# schematic-version3_-_Jigbin.net
KiCad netlist of a schematic drawn in EAGLE
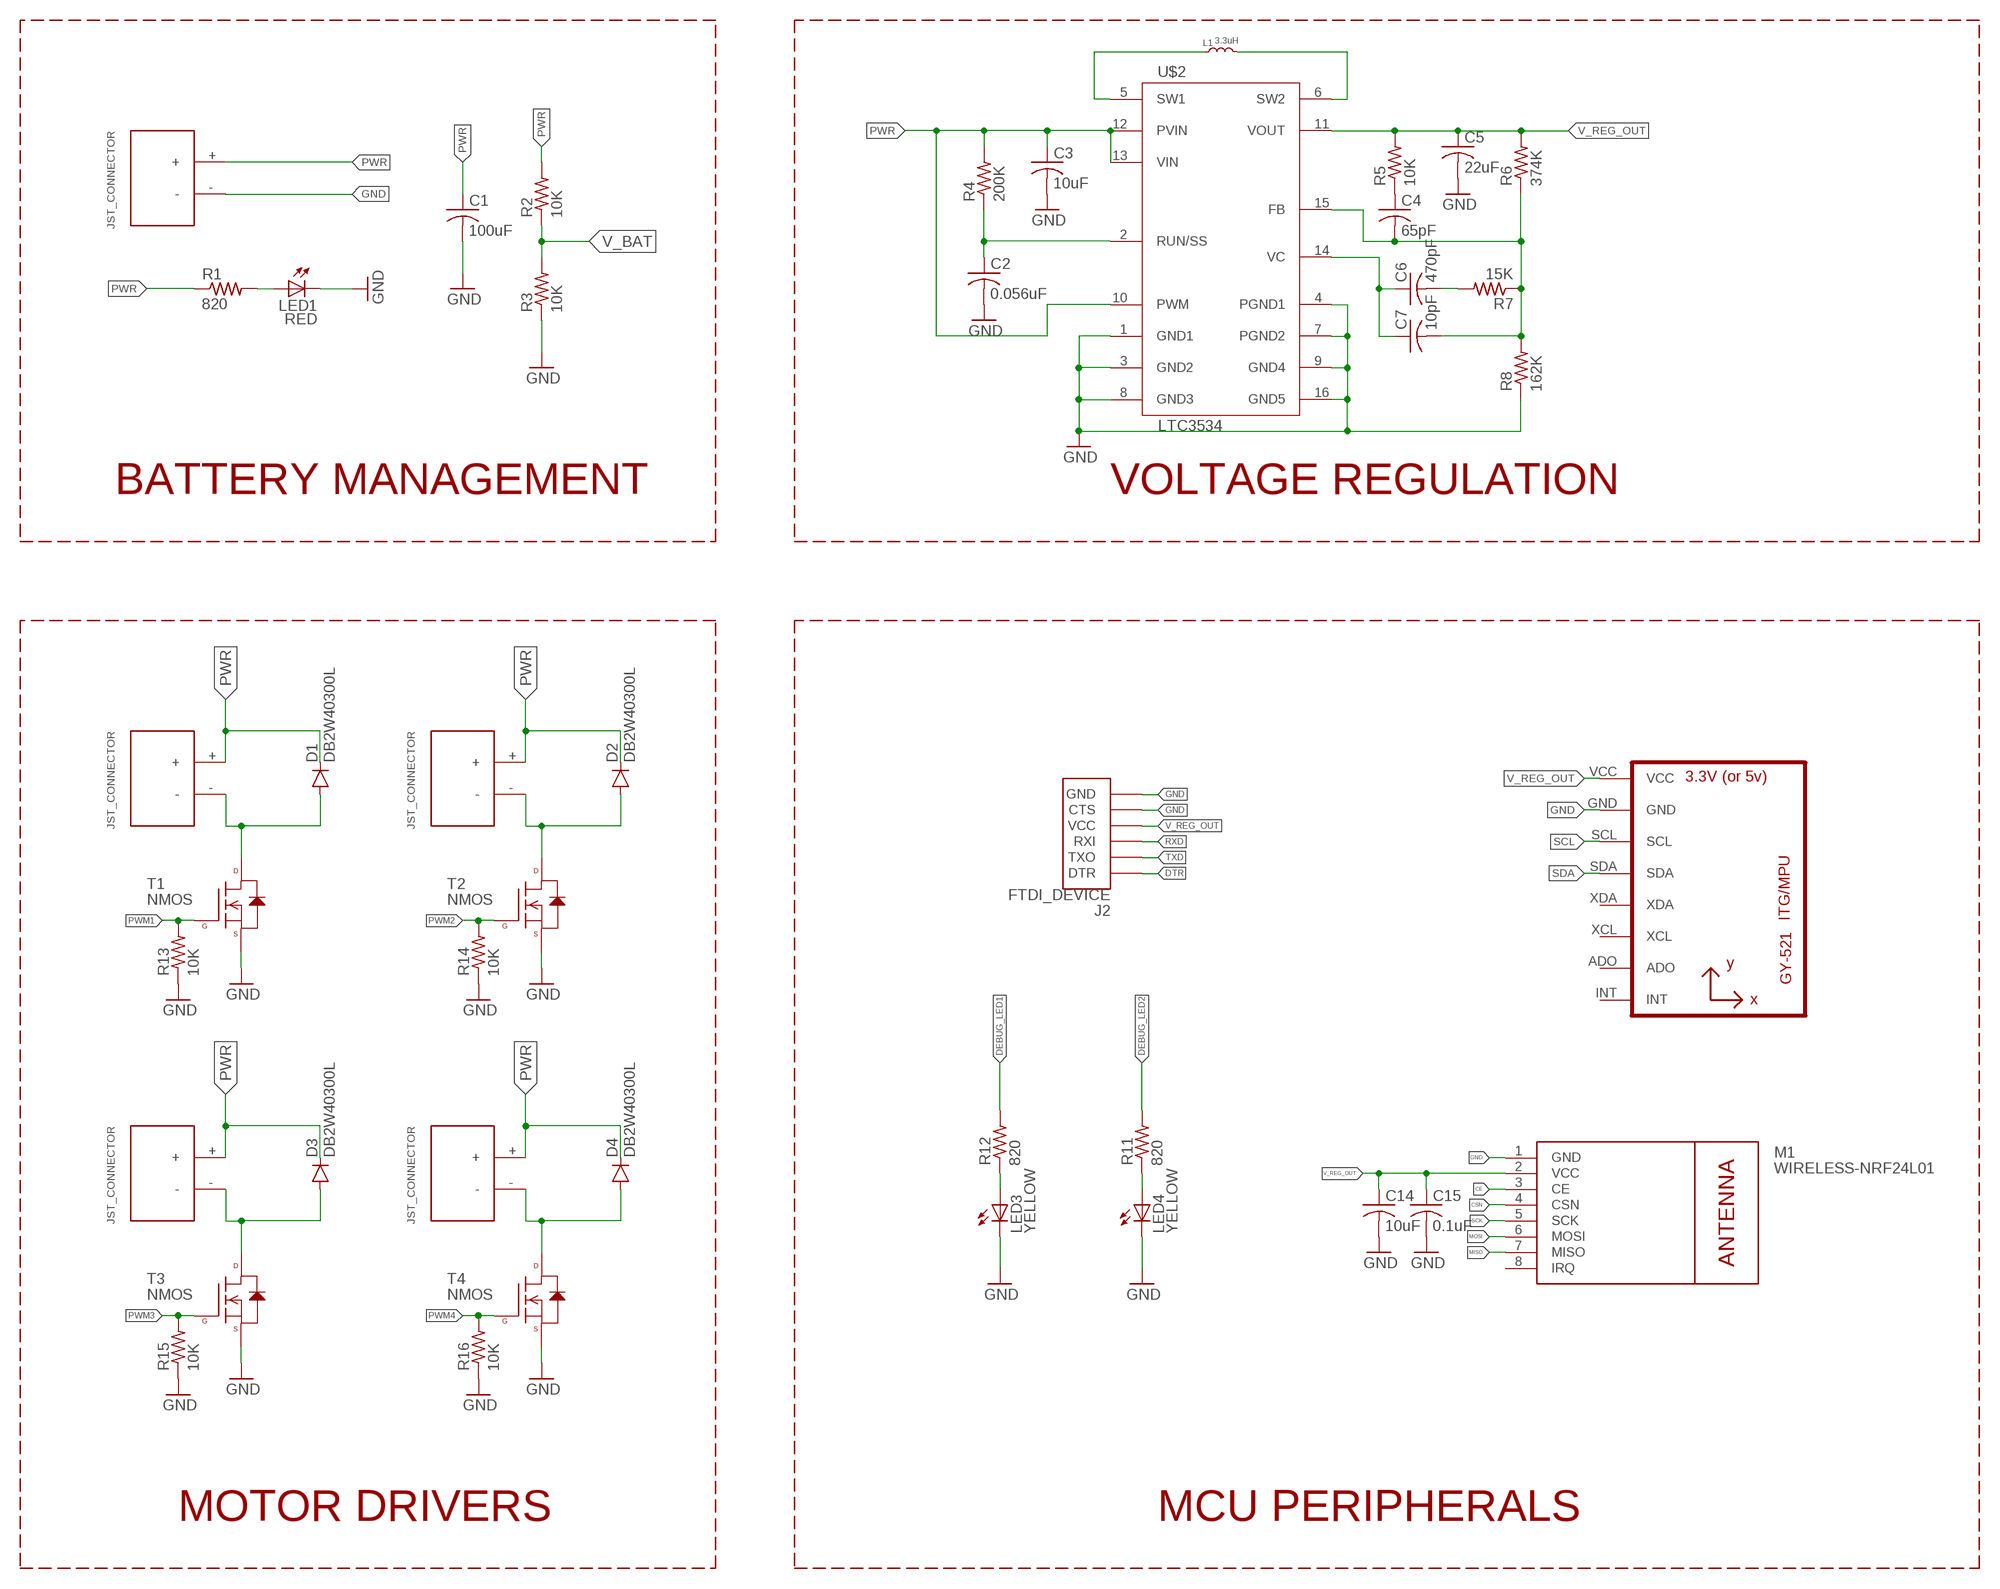
[diagram p0: schematic, sheet 1, part 1 of 2]
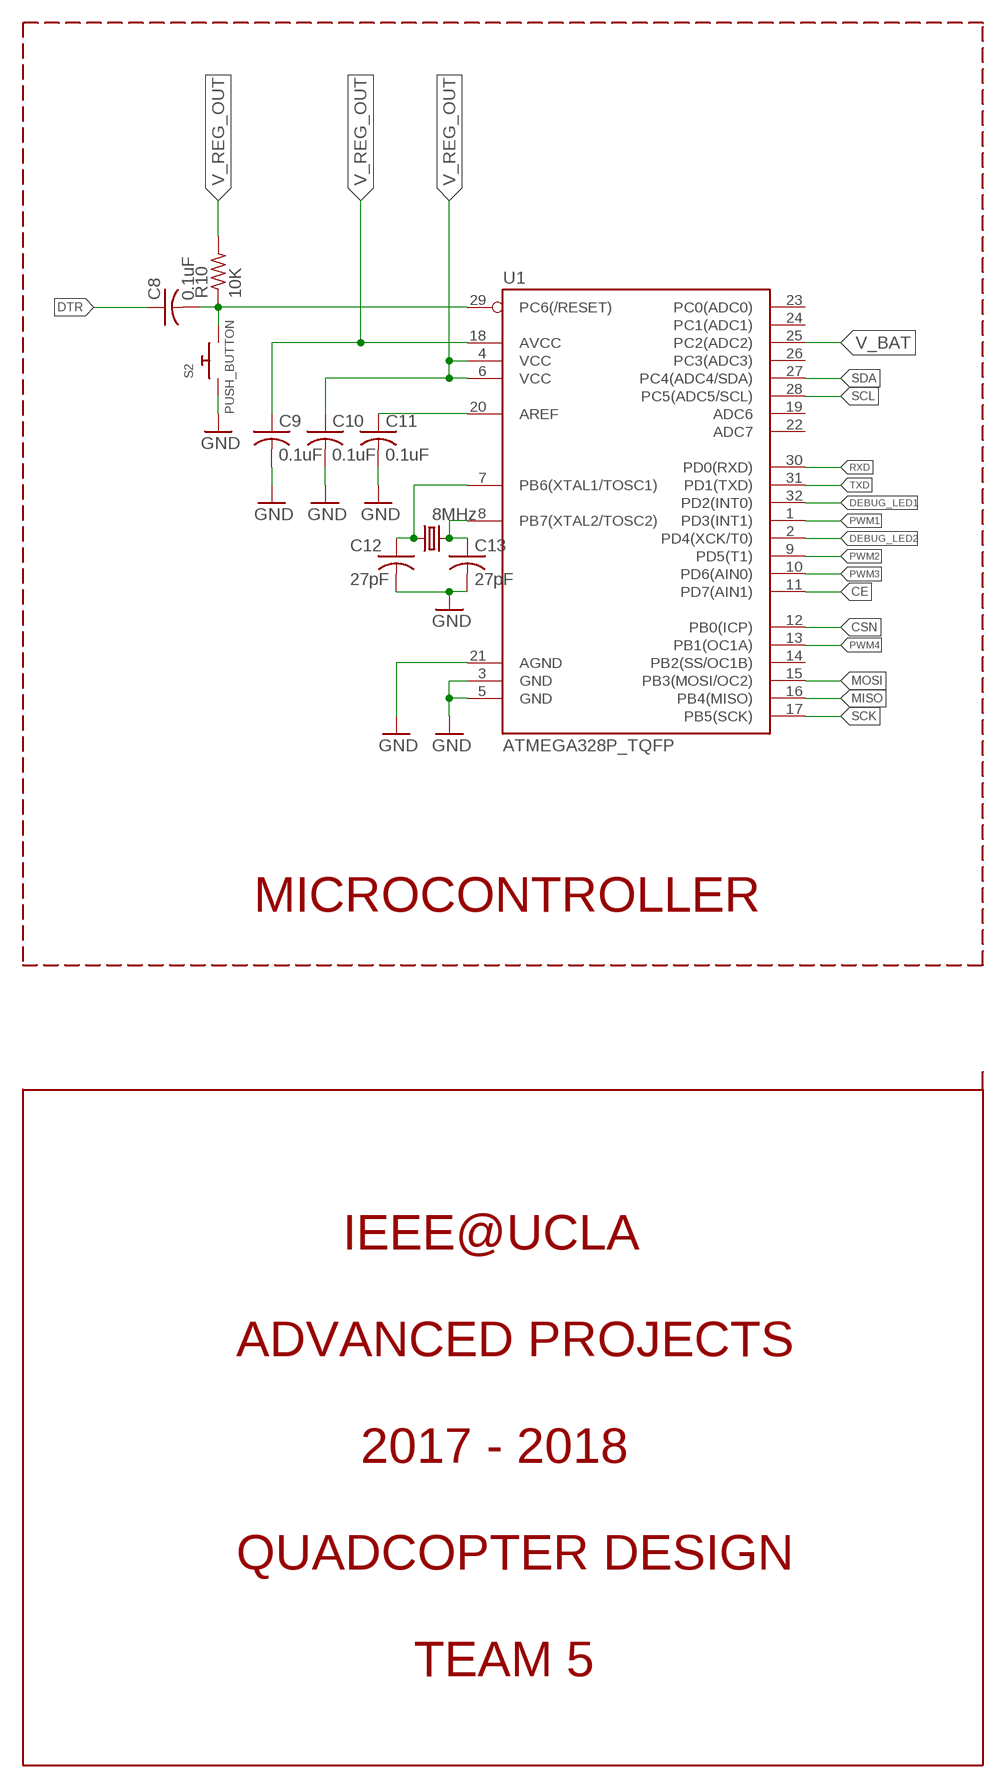
[diagram p1: schematic, sheet 1, part 2 of 2]

(export (version "E")
  (design (tool "Eeschema 10.0.6"))
  (components
    (comp (ref "C1")
      (value "100uF")
      (footprint "eagle-import:C1210")
      (libsource (lib "eagle-import") (part "C-USC1210"))
    )
    (comp (ref "C2")
      (value "0.056uF")
      (footprint "eagle-import:C0603")
      (libsource (lib "eagle-import") (part "resistor_348_C-USC0603"))
    )
    (comp (ref "C3")
      (value "10uF")
      (footprint "eagle-import:C0603")
      (libsource (lib "eagle-import") (part "resistor_348_C-USC0603"))
    )
    (comp (ref "C4")
      (value "65pF")
      (footprint "eagle-import:C1206")
      (libsource (lib "eagle-import") (part "C-USC1206"))
    )
    (comp (ref "C5")
      (value "22uF")
      (footprint "eagle-import:C0603")
      (libsource (lib "eagle-import") (part "resistor_348_C-USC0603"))
    )
    (comp (ref "C6")
      (value "470pF")
      (footprint "eagle-import:C0603")
      (libsource (lib "eagle-import") (part "resistor_348_C-USC0603"))
    )
    (comp (ref "C7")
      (value "10pF")
      (footprint "eagle-import:C0603")
      (libsource (lib "eagle-import") (part "resistor_348_C-USC0603"))
    )
    (comp (ref "C8")
      (value "0.1uF")
      (footprint "eagle-import:C0603")
      (libsource (lib "eagle-import") (part "C-USC0603"))
    )
    (comp (ref "C9")
      (value "0.1uF")
      (footprint "eagle-import:C0603")
      (libsource (lib "eagle-import") (part "C-USC0603"))
    )
    (comp (ref "C10")
      (value "0.1uF")
      (footprint "eagle-import:C0603")
      (libsource (lib "eagle-import") (part "C-USC0603"))
    )
    (comp (ref "C11")
      (value "0.1uF")
      (footprint "eagle-import:C0603")
      (libsource (lib "eagle-import") (part "C-USC0603"))
    )
    (comp (ref "C12")
      (value "27pF")
      (footprint "eagle-import:C0603")
      (libsource (lib "eagle-import") (part "resistor_348_C-USC0603"))
    )
    (comp (ref "C13")
      (value "27pF")
      (footprint "eagle-import:C0603")
      (libsource (lib "eagle-import") (part "resistor_348_C-USC0603"))
    )
    (comp (ref "C14")
      (value "10uF")
      (footprint "eagle-import:C0603")
      (libsource (lib "eagle-import") (part "resistor_348_C-USC0603"))
    )
    (comp (ref "C15")
      (value "0.1uF")
      (footprint "eagle-import:C0603")
      (libsource (lib "eagle-import") (part "resistor_348_C-USC0603"))
    )
    (comp (ref "D1")
      (value "DB2W40300L")
      (footprint "eagle-import:MINI2-F3-B")
      (libsource (lib "eagle-import") (part "DB2W40300L"))
    )
    (comp (ref "D2")
      (value "DB2W40300L")
      (footprint "eagle-import:MINI2-F3-B")
      (libsource (lib "eagle-import") (part "DB2W40300L"))
    )
    (comp (ref "D3")
      (value "DB2W40300L")
      (footprint "eagle-import:MINI2-F3-B")
      (libsource (lib "eagle-import") (part "DB2W40300L"))
    )
    (comp (ref "D4")
      (value "DB2W40300L")
      (footprint "eagle-import:MINI2-F3-B")
      (libsource (lib "eagle-import") (part "DB2W40300L"))
    )
    (comp (ref "J2")
      (value "FTDI_DEVICE")
      (footprint "eagle-import:FTDI_DEVICE_SIDE")
      (libsource (lib "eagle-import") (part "FTDI_DEVICE"))
    )
    (comp (ref "L1")
      (value "3.3uH")
      (footprint "eagle-import:XAL4020")
      (libsource (lib "eagle-import") (part "INDUCTOR.XAL4020"))
    )
    (comp (ref "LED1")
      (value "RED")
      (footprint "eagle-import:SML0603")
      (libsource (lib "eagle-import") (part "LEDSML0603"))
    )
    (comp (ref "LED3")
      (value "YELLOW")
      (footprint "eagle-import:SML0603")
      (libsource (lib "eagle-import") (part "LEDSML0603"))
    )
    (comp (ref "LED4")
      (value "YELLOW")
      (footprint "eagle-import:SML0603")
      (libsource (lib "eagle-import") (part "LEDSML0603"))
    )
    (comp (ref "M1")
      (value "WIRELESS-NRF24L01")
      (footprint "eagle-import:WIRELESS-NRF24L01")
      (libsource (lib "eagle-import") (part "WIRELESS-NRF24L01"))
    )
    (comp (ref "Q1")
      (value "8MHz")
      (footprint "eagle-import:CSM-7X-DU")
      (libsource (lib "eagle-import") (part "CSM-7X-DU"))
    )
    (comp (ref "R1")
      (value "820")
      (footprint "eagle-import:R0603")
      (libsource (lib "eagle-import") (part "R-US_R0603"))
    )
    (comp (ref "R2")
      (value "10K")
      (footprint "eagle-import:R0603")
      (libsource (lib "eagle-import") (part "resistor_348_R-US_R0603"))
    )
    (comp (ref "R3")
      (value "10K")
      (footprint "eagle-import:R0603")
      (libsource (lib "eagle-import") (part "resistor_348_R-US_R0603"))
    )
    (comp (ref "R4")
      (value "200K")
      (footprint "eagle-import:R0603")
      (libsource (lib "eagle-import") (part "resistor_348_R-US_R0603"))
    )
    (comp (ref "R5")
      (value "10K")
      (footprint "eagle-import:R0603")
      (libsource (lib "eagle-import") (part "resistor_348_R-US_R0603"))
    )
    (comp (ref "R6")
      (value "374K")
      (footprint "eagle-import:R0603")
      (libsource (lib "eagle-import") (part "resistor_348_R-US_R0603"))
    )
    (comp (ref "R7")
      (value "15K")
      (footprint "eagle-import:R0603")
      (libsource (lib "eagle-import") (part "resistor_348_R-US_R0603"))
    )
    (comp (ref "R8")
      (value "162K")
      (footprint "eagle-import:R0603")
      (libsource (lib "eagle-import") (part "resistor_348_R-US_R0603"))
    )
    (comp (ref "R10")
      (value "10K")
      (footprint "eagle-import:R0603")
      (libsource (lib "eagle-import") (part "resistor_348_R-US_R0603"))
    )
    (comp (ref "R11")
      (value "820")
      (footprint "eagle-import:R0603")
      (libsource (lib "eagle-import") (part "R-US_R0603"))
    )
    (comp (ref "R12")
      (value "820")
      (footprint "eagle-import:R0603")
      (libsource (lib "eagle-import") (part "R-US_R0603"))
    )
    (comp (ref "R13")
      (value "10K")
      (footprint "eagle-import:R0603")
      (libsource (lib "eagle-import") (part "resistor_348_R-US_R0603"))
    )
    (comp (ref "R14")
      (value "10K")
      (footprint "eagle-import:R0603")
      (libsource (lib "eagle-import") (part "resistor_348_R-US_R0603"))
    )
    (comp (ref "R15")
      (value "10K")
      (footprint "eagle-import:R0603")
      (libsource (lib "eagle-import") (part "resistor_348_R-US_R0603"))
    )
    (comp (ref "R16")
      (value "10K")
      (footprint "eagle-import:R0603")
      (libsource (lib "eagle-import") (part "resistor_348_R-US_R0603"))
    )
    (comp (ref "S2")
      (value "PUSH_BUTTON")
      (footprint "eagle-import:PUSHBUTTON_SMD_SJ")
      (libsource (lib "eagle-import") (part "SWITCH_PUSHBUTTONSOFTTOUCHSMD_SJ"))
    )
    (comp (ref "T1")
      (value "NMOS")
      (footprint "eagle-import:SOT23-3")
      (libsource (lib "eagle-import") (part "N-CHANNEL-MOSFET-IRLML6244TRPBF"))
    )
    (comp (ref "T2")
      (value "NMOS")
      (footprint "eagle-import:SOT23-3")
      (libsource (lib "eagle-import") (part "N-CHANNEL-MOSFET-IRLML6244TRPBF"))
    )
    (comp (ref "T3")
      (value "NMOS")
      (footprint "eagle-import:SOT23-3")
      (libsource (lib "eagle-import") (part "N-CHANNEL-MOSFET-IRLML6244TRPBF"))
    )
    (comp (ref "T4")
      (value "NMOS")
      (footprint "eagle-import:SOT23-3")
      (libsource (lib "eagle-import") (part "N-CHANNEL-MOSFET-IRLML6244TRPBF"))
    )
    (comp (ref "U$1")
      (value "JST_CONNECTOR_FEMALE")
      (footprint "eagle-import:JST_CONNECTOR_FEMALE")
      (libsource (lib "eagle-import") (part "JST_CONNECTOR_FEMALE"))
    )
    (comp (ref "U$2")
      (value "LTC3534")
      (footprint "eagle-import:SSOP-16GN")
      (libsource (lib "eagle-import") (part "LTC3534"))
    )
    (comp (ref "U$4")
      (value "JST_CONNECTOR_FEMALE")
      (footprint "eagle-import:JST_CONNECTOR_FEMALE")
      (libsource (lib "eagle-import") (part "JST_CONNECTOR_FEMALE"))
    )
    (comp (ref "U$7")
      (value "JST_CONNECTOR_FEMALE")
      (footprint "eagle-import:JST_CONNECTOR_FEMALE")
      (libsource (lib "eagle-import") (part "JST_CONNECTOR_FEMALE"))
    )
    (comp (ref "U$10")
      (value "JST_CONNECTOR_FEMALE")
      (footprint "eagle-import:JST_CONNECTOR_FEMALE")
      (libsource (lib "eagle-import") (part "JST_CONNECTOR_FEMALE"))
    )
    (comp (ref "U$13")
      (value "JST_CONNECTOR_FEMALE")
      (footprint "eagle-import:JST_CONNECTOR_FEMALE")
      (libsource (lib "eagle-import") (part "JST_CONNECTOR_FEMALE"))
    )
    (comp (ref "U1")
      (value "ATMEGA328P_TQFP")
      (footprint "eagle-import:TQFP32-08")
      (libsource (lib "eagle-import") (part "ATMEGA328P_TQFP"))
    )
    (comp (ref "U2")
      (value "GY-521MPU6050")
      (footprint "eagle-import:GY-521")
      (libsource (lib "eagle-import") (part "GY-521MPU6050"))
    )
  )
  (nets
    (net (code "1") (name "CE") (class "Default")
      (node (ref "M1") (pin "3") (pinfunction "CE_3") (pintype "bidirectional"))
      (node (ref "U1") (pin "11") (pinfunction "PD7(AIN1)_11") (pintype "bidirectional"))
    )
    (net (code "2") (name "CSN") (class "Default")
      (node (ref "M1") (pin "4") (pinfunction "CSN_4") (pintype "bidirectional"))
      (node (ref "U1") (pin "12") (pinfunction "PB0(ICP)_12") (pintype "bidirectional"))
    )
    (net (code "3") (name "DEBUG_LED1") (class "Default")
      (node (ref "R12") (pin "2") (pinfunction "2_2") (pintype "passive"))
      (node (ref "U1") (pin "32") (pinfunction "PD2(INT0)_32") (pintype "bidirectional"))
    )
    (net (code "4") (name "DEBUG_LED2") (class "Default")
      (node (ref "R11") (pin "2") (pinfunction "2_2") (pintype "passive"))
      (node (ref "U1") (pin "2") (pinfunction "PD4(XCK/T0)_2") (pintype "bidirectional"))
    )
    (net (code "5") (name "DTR") (class "Default")
      (node (ref "C8") (pin "1") (pinfunction "1_1") (pintype "passive"))
      (node (ref "J2") (pin "P$1") (pinfunction "DTR_P$1") (pintype "bidirectional"))
    )
    (net (code "6") (name "GND") (class "Default")
      (node (ref "C1") (pin "2") (pinfunction "2_2") (pintype "passive"))
      (node (ref "C10") (pin "2") (pinfunction "2_2") (pintype "passive"))
      (node (ref "C11") (pin "2") (pinfunction "2_2") (pintype "passive"))
      (node (ref "C12") (pin "2") (pinfunction "2_2") (pintype "passive"))
      (node (ref "C13") (pin "2") (pinfunction "2_2") (pintype "passive"))
      (node (ref "C14") (pin "2") (pinfunction "2_2") (pintype "passive"))
      (node (ref "C15") (pin "2") (pinfunction "2_2") (pintype "passive"))
      (node (ref "C2") (pin "2") (pinfunction "2_2") (pintype "passive"))
      (node (ref "C3") (pin "2") (pinfunction "2_2") (pintype "passive"))
      (node (ref "C5") (pin "2") (pinfunction "2_2") (pintype "passive"))
      (node (ref "C9") (pin "2") (pinfunction "2_2") (pintype "passive"))
      (node (ref "J2") (pin "P$5") (pinfunction "CTS_P$5") (pintype "bidirectional"))
      (node (ref "J2") (pin "P$6") (pinfunction "GND_P$6") (pintype "bidirectional"))
      (node (ref "LED1") (pin "C") (pinfunction "C_C") (pintype "passive"))
      (node (ref "LED3") (pin "C") (pinfunction "C_C") (pintype "passive"))
      (node (ref "LED4") (pin "C") (pinfunction "C_C") (pintype "passive"))
      (node (ref "M1") (pin "1") (pinfunction "GND_1") (pintype "power_in"))
      (node (ref "R13") (pin "1") (pinfunction "1_1") (pintype "passive"))
      (node (ref "R14") (pin "1") (pinfunction "1_1") (pintype "passive"))
      (node (ref "R15") (pin "1") (pinfunction "1_1") (pintype "passive"))
      (node (ref "R16") (pin "1") (pinfunction "1_1") (pintype "passive"))
      (node (ref "R3") (pin "1") (pinfunction "1_1") (pintype "passive"))
      (node (ref "R8") (pin "1") (pinfunction "1_1") (pintype "passive"))
      (node (ref "S2") (pin "P$1") (pinfunction "P$1_P$1") (pintype "passive"))
      (node (ref "T1") (pin "2") (pinfunction "S_2") (pintype "passive"))
      (node (ref "T2") (pin "2") (pinfunction "S_2") (pintype "passive"))
      (node (ref "T3") (pin "2") (pinfunction "S_2") (pintype "passive"))
      (node (ref "T4") (pin "2") (pinfunction "S_2") (pintype "passive"))
      (node (ref "U$1") (pin "-") (pinfunction "-_-") (pintype "bidirectional"))
      (node (ref "U$2") (pin "1") (pinfunction "GND1_1") (pintype "bidirectional"))
      (node (ref "U$2") (pin "16") (pinfunction "GND5_16") (pintype "bidirectional"))
      (node (ref "U$2") (pin "3") (pinfunction "GND2_3") (pintype "bidirectional"))
      (node (ref "U$2") (pin "4") (pinfunction "PGND1_4") (pintype "bidirectional"))
      (node (ref "U$2") (pin "7") (pinfunction "PGND2_7") (pintype "bidirectional"))
      (node (ref "U$2") (pin "8") (pinfunction "GND3_8") (pintype "bidirectional"))
      (node (ref "U$2") (pin "9") (pinfunction "GND4_9") (pintype "bidirectional"))
      (node (ref "U1") (pin "21") (pinfunction "AGND_21") (pintype "bidirectional"))
      (node (ref "U1") (pin "3") (pinfunction "GND_3") (pintype "bidirectional"))
      (node (ref "U1") (pin "5") (pinfunction "GND_5") (pintype "bidirectional"))
      (node (ref "U2") (pin "GND") (pinfunction "GND_GND") (pintype "bidirectional"))
    )
    (net (code "7") (name "MISO") (class "Default")
      (node (ref "M1") (pin "7") (pinfunction "MISO_7") (pintype "bidirectional"))
      (node (ref "U1") (pin "16") (pinfunction "PB4(MISO)_16") (pintype "bidirectional"))
    )
    (net (code "8") (name "MOSI") (class "Default")
      (node (ref "M1") (pin "6") (pinfunction "MOSI_6") (pintype "bidirectional"))
      (node (ref "U1") (pin "15") (pinfunction "PB3(MOSI/OC2)_15") (pintype "bidirectional"))
    )
    (net (code "9") (name "Net-(C4-Pad1)") (class "Default")
      (node (ref "C4") (pin "1") (pinfunction "1_1") (pintype "passive"))
      (node (ref "R5") (pin "1") (pinfunction "1_1") (pintype "passive"))
    )
    (net (code "10") (name "Net-(C6-Pad2)") (class "Default")
      (node (ref "C6") (pin "2") (pinfunction "2_2") (pintype "passive"))
      (node (ref "R7") (pin "2") (pinfunction "2_2") (pintype "passive"))
    )
    (net (code "11") (name "Net-(D1-PPIN)") (class "Default")
      (node (ref "D1") (pin "POS") (pinfunction "PPIN_POS") (pintype "passive"))
      (node (ref "T1") (pin "3") (pinfunction "D_3") (pintype "passive"))
      (node (ref "U$4") (pin "-") (pinfunction "-_-") (pintype "bidirectional"))
    )
    (net (code "12") (name "Net-(D2-PPIN)") (class "Default")
      (node (ref "D2") (pin "POS") (pinfunction "PPIN_POS") (pintype "passive"))
      (node (ref "T2") (pin "3") (pinfunction "D_3") (pintype "passive"))
      (node (ref "U$7") (pin "-") (pinfunction "-_-") (pintype "bidirectional"))
    )
    (net (code "13") (name "Net-(D3-PPIN)") (class "Default")
      (node (ref "D3") (pin "POS") (pinfunction "PPIN_POS") (pintype "passive"))
      (node (ref "T3") (pin "3") (pinfunction "D_3") (pintype "passive"))
      (node (ref "U$10") (pin "-") (pinfunction "-_-") (pintype "bidirectional"))
    )
    (net (code "14") (name "Net-(D4-PPIN)") (class "Default")
      (node (ref "D4") (pin "POS") (pinfunction "PPIN_POS") (pintype "passive"))
      (node (ref "T4") (pin "3") (pinfunction "D_3") (pintype "passive"))
      (node (ref "U$13") (pin "-") (pinfunction "-_-") (pintype "bidirectional"))
    )
    (net (code "15") (name "Net-(LED1-PadA)") (class "Default")
      (node (ref "LED1") (pin "A") (pinfunction "A_A") (pintype "passive"))
      (node (ref "R1") (pin "2") (pinfunction "2_2") (pintype "passive"))
    )
    (net (code "16") (name "Net-(LED3-PadA)") (class "Default")
      (node (ref "LED3") (pin "A") (pinfunction "A_A") (pintype "passive"))
      (node (ref "R12") (pin "1") (pinfunction "1_1") (pintype "passive"))
    )
    (net (code "17") (name "Net-(LED4-PadA)") (class "Default")
      (node (ref "LED4") (pin "A") (pinfunction "A_A") (pintype "passive"))
      (node (ref "R11") (pin "1") (pinfunction "1_1") (pintype "passive"))
    )
    (net (code "18") (name "Net-(U$2-FB)") (class "Default")
      (node (ref "C4") (pin "2") (pinfunction "2_2") (pintype "passive"))
      (node (ref "C7") (pin "2") (pinfunction "2_2") (pintype "passive"))
      (node (ref "R6") (pin "1") (pinfunction "1_1") (pintype "passive"))
      (node (ref "R7") (pin "1") (pinfunction "1_1") (pintype "passive"))
      (node (ref "R8") (pin "2") (pinfunction "2_2") (pintype "passive"))
      (node (ref "U$2") (pin "15") (pinfunction "FB_15") (pintype "bidirectional"))
    )
    (net (code "19") (name "Net-(U$2-RUN{slash}SS)") (class "Default")
      (node (ref "C2") (pin "1") (pinfunction "1_1") (pintype "passive"))
      (node (ref "R4") (pin "1") (pinfunction "1_1") (pintype "passive"))
      (node (ref "U$2") (pin "2") (pinfunction "RUN/SS_2") (pintype "bidirectional"))
    )
    (net (code "20") (name "Net-(U$2-SW1)") (class "Default")
      (node (ref "L1") (pin "1") (pinfunction "1_1") (pintype "passive"))
      (node (ref "U$2") (pin "5") (pinfunction "SW1_5") (pintype "bidirectional"))
    )
    (net (code "21") (name "Net-(U$2-SW2)") (class "Default")
      (node (ref "L1") (pin "2") (pinfunction "2_2") (pintype "passive"))
      (node (ref "U$2") (pin "6") (pinfunction "SW2_6") (pintype "bidirectional"))
    )
    (net (code "22") (name "Net-(U$2-VC)") (class "Default")
      (node (ref "C6") (pin "1") (pinfunction "1_1") (pintype "passive"))
      (node (ref "C7") (pin "1") (pinfunction "1_1") (pintype "passive"))
      (node (ref "U$2") (pin "14") (pinfunction "VC_14") (pintype "bidirectional"))
    )
    (net (code "23") (name "Net-(U1-AREF)") (class "Default")
      (node (ref "C11") (pin "1") (pinfunction "1_1") (pintype "passive"))
      (node (ref "U1") (pin "20") (pinfunction "AREF_20") (pintype "bidirectional"))
    )
    (net (code "24") (name "Net-(U1-PB6(XTAL1{slash}TOSC1))") (class "Default")
      (node (ref "C12") (pin "1") (pinfunction "1_1") (pintype "passive"))
      (node (ref "Q1") (pin "1") (pinfunction "1_1") (pintype "passive"))
      (node (ref "U1") (pin "7") (pinfunction "PB6(XTAL1/TOSC1)_7") (pintype "bidirectional"))
    )
    (net (code "25") (name "Net-(U1-PB7(XTAL2{slash}TOSC2))") (class "Default")
      (node (ref "C13") (pin "1") (pinfunction "1_1") (pintype "passive"))
      (node (ref "Q1") (pin "2") (pinfunction "2_2") (pintype "passive"))
      (node (ref "U1") (pin "8") (pinfunction "PB7(XTAL2/TOSC2)_8") (pintype "bidirectional"))
    )
    (net (code "26") (name "Net-(U1-PC6({slash}RESET))") (class "Default")
      (node (ref "C8") (pin "2") (pinfunction "2_2") (pintype "passive"))
      (node (ref "R10") (pin "1") (pinfunction "1_1") (pintype "passive"))
      (node (ref "S2") (pin "P$2") (pinfunction "P$2_P$2") (pintype "passive"))
      (node (ref "U1") (pin "29") (pinfunction "PC6(/RESET)_29") (pintype "bidirectional"))
    )
    (net (code "27") (name "PWM1") (class "Default")
      (node (ref "R13") (pin "2") (pinfunction "2_2") (pintype "passive"))
      (node (ref "T1") (pin "1") (pinfunction "G_1") (pintype "passive"))
      (node (ref "U1") (pin "1") (pinfunction "PD3(INT1)_1") (pintype "bidirectional"))
    )
    (net (code "28") (name "PWM2") (class "Default")
      (node (ref "R14") (pin "2") (pinfunction "2_2") (pintype "passive"))
      (node (ref "T2") (pin "1") (pinfunction "G_1") (pintype "passive"))
      (node (ref "U1") (pin "9") (pinfunction "PD5(T1)_9") (pintype "bidirectional"))
    )
    (net (code "29") (name "PWM3") (class "Default")
      (node (ref "R15") (pin "2") (pinfunction "2_2") (pintype "passive"))
      (node (ref "T3") (pin "1") (pinfunction "G_1") (pintype "passive"))
      (node (ref "U1") (pin "10") (pinfunction "PD6(AIN0)_10") (pintype "bidirectional"))
    )
    (net (code "30") (name "PWM4") (class "Default")
      (node (ref "R16") (pin "2") (pinfunction "2_2") (pintype "passive"))
      (node (ref "T4") (pin "1") (pinfunction "G_1") (pintype "passive"))
      (node (ref "U1") (pin "13") (pinfunction "PB1(OC1A)_13") (pintype "bidirectional"))
    )
    (net (code "31") (name "PWR") (class "Default")
      (node (ref "C1") (pin "1") (pinfunction "1_1") (pintype "passive"))
      (node (ref "C3") (pin "1") (pinfunction "1_1") (pintype "passive"))
      (node (ref "D1") (pin "NEG") (pinfunction "GPIN_NEG") (pintype "passive"))
      (node (ref "D2") (pin "NEG") (pinfunction "GPIN_NEG") (pintype "passive"))
      (node (ref "D3") (pin "NEG") (pinfunction "GPIN_NEG") (pintype "passive"))
      (node (ref "D4") (pin "NEG") (pinfunction "GPIN_NEG") (pintype "passive"))
      (node (ref "R1") (pin "1") (pinfunction "1_1") (pintype "passive"))
      (node (ref "R2") (pin "2") (pinfunction "2_2") (pintype "passive"))
      (node (ref "R4") (pin "2") (pinfunction "2_2") (pintype "passive"))
      (node (ref "U$1") (pin "+") (pinfunction "+_+") (pintype "bidirectional"))
      (node (ref "U$10") (pin "+") (pinfunction "+_+") (pintype "bidirectional"))
      (node (ref "U$13") (pin "+") (pinfunction "+_+") (pintype "bidirectional"))
      (node (ref "U$2") (pin "10") (pinfunction "PWM_10") (pintype "bidirectional"))
      (node (ref "U$2") (pin "12") (pinfunction "PVIN_12") (pintype "bidirectional"))
      (node (ref "U$2") (pin "13") (pinfunction "VIN_13") (pintype "bidirectional"))
      (node (ref "U$4") (pin "+") (pinfunction "+_+") (pintype "bidirectional"))
      (node (ref "U$7") (pin "+") (pinfunction "+_+") (pintype "bidirectional"))
    )
    (net (code "32") (name "RXD") (class "Default")
      (node (ref "J2") (pin "P$3") (pinfunction "RXI_P$3") (pintype "bidirectional"))
      (node (ref "U1") (pin "30") (pinfunction "PD0(RXD)_30") (pintype "bidirectional"))
    )
    (net (code "33") (name "SCK") (class "Default")
      (node (ref "M1") (pin "5") (pinfunction "SCK_5") (pintype "bidirectional"))
      (node (ref "U1") (pin "17") (pinfunction "PB5(SCK)_17") (pintype "bidirectional"))
    )
    (net (code "34") (name "SCL") (class "Default")
      (node (ref "U1") (pin "28") (pinfunction "PC5(ADC5/SCL)_28") (pintype "bidirectional"))
      (node (ref "U2") (pin "SCL") (pinfunction "SCL_SCL") (pintype "bidirectional"))
    )
    (net (code "35") (name "SDA") (class "Default")
      (node (ref "U1") (pin "27") (pinfunction "PC4(ADC4/SDA)_27") (pintype "bidirectional"))
      (node (ref "U2") (pin "SDA") (pinfunction "SDA_SDA") (pintype "bidirectional"))
    )
    (net (code "36") (name "TXD") (class "Default")
      (node (ref "J2") (pin "P$2") (pinfunction "TXO_P$2") (pintype "bidirectional"))
      (node (ref "U1") (pin "31") (pinfunction "PD1(TXD)_31") (pintype "bidirectional"))
    )
    (net (code "37") (name "V_BAT") (class "Default")
      (node (ref "R2") (pin "1") (pinfunction "1_1") (pintype "passive"))
      (node (ref "R3") (pin "2") (pinfunction "2_2") (pintype "passive"))
      (node (ref "U1") (pin "25") (pinfunction "PC2(ADC2)_25") (pintype "bidirectional"))
    )
    (net (code "38") (name "V_REG_OUT") (class "Default")
      (node (ref "C10") (pin "1") (pinfunction "1_1") (pintype "passive"))
      (node (ref "C14") (pin "1") (pinfunction "1_1") (pintype "passive"))
      (node (ref "C15") (pin "1") (pinfunction "1_1") (pintype "passive"))
      (node (ref "C5") (pin "1") (pinfunction "1_1") (pintype "passive"))
      (node (ref "C9") (pin "1") (pinfunction "1_1") (pintype "passive"))
      (node (ref "J2") (pin "P$4") (pinfunction "VCC_P$4") (pintype "bidirectional"))
      (node (ref "M1") (pin "2") (pinfunction "VCC_2") (pintype "power_in"))
      (node (ref "R10") (pin "2") (pinfunction "2_2") (pintype "passive"))
      (node (ref "R5") (pin "2") (pinfunction "2_2") (pintype "passive"))
      (node (ref "R6") (pin "2") (pinfunction "2_2") (pintype "passive"))
      (node (ref "U$2") (pin "11") (pinfunction "VOUT_11") (pintype "bidirectional"))
      (node (ref "U1") (pin "18") (pinfunction "AVCC_18") (pintype "bidirectional"))
      (node (ref "U1") (pin "4") (pinfunction "VCC_4") (pintype "bidirectional"))
      (node (ref "U1") (pin "6") (pinfunction "VCC_6") (pintype "bidirectional"))
      (node (ref "U2") (pin "VCC") (pinfunction "VCC_VCC") (pintype "bidirectional"))
    )
    (net (code "39") (name "unconnected-(M1-IRQ-Pad8)") (class "Default")
      (node (ref "M1") (pin "8") (pinfunction "IRQ_8") (pintype "bidirectional"))
    )
    (net (code "40") (name "unconnected-(U1-ADC6-Pad19)") (class "Default")
      (node (ref "U1") (pin "19") (pinfunction "ADC6_19") (pintype "bidirectional"))
    )
    (net (code "41") (name "unconnected-(U1-ADC7-Pad22)") (class "Default")
      (node (ref "U1") (pin "22") (pinfunction "ADC7_22") (pintype "bidirectional"))
    )
    (net (code "42") (name "unconnected-(U1-PB2(SS{slash}OC1B)-Pad14)") (class "Default")
      (node (ref "U1") (pin "14") (pinfunction "PB2(SS/OC1B)_14") (pintype "bidirectional"))
    )
    (net (code "43") (name "unconnected-(U1-PC0(ADC0)-Pad23)") (class "Default")
      (node (ref "U1") (pin "23") (pinfunction "PC0(ADC0)_23") (pintype "bidirectional"))
    )
    (net (code "44") (name "unconnected-(U1-PC1(ADC1)-Pad24)") (class "Default")
      (node (ref "U1") (pin "24") (pinfunction "PC1(ADC1)_24") (pintype "bidirectional"))
    )
    (net (code "45") (name "unconnected-(U1-PC3(ADC3)-Pad26)") (class "Default")
      (node (ref "U1") (pin "26") (pinfunction "PC3(ADC3)_26") (pintype "bidirectional"))
    )
    (net (code "46") (name "unconnected-(U2-PadADO)") (class "Default")
      (node (ref "U2") (pin "ADO") (pinfunction "ADO_ADO") (pintype "bidirectional"))
    )
    (net (code "47") (name "unconnected-(U2-PadINT)") (class "Default")
      (node (ref "U2") (pin "INT") (pinfunction "INT_INT") (pintype "bidirectional"))
    )
    (net (code "48") (name "unconnected-(U2-PadXCL)") (class "Default")
      (node (ref "U2") (pin "XCL") (pinfunction "XCL_XCL") (pintype "bidirectional"))
    )
    (net (code "49") (name "unconnected-(U2-PadXDA)") (class "Default")
      (node (ref "U2") (pin "XDA") (pinfunction "XDA_XDA") (pintype "bidirectional"))
    )
  )
)
